# ubus_rev_b.net
KiCad netlist of a schematic drawn in EAGLE
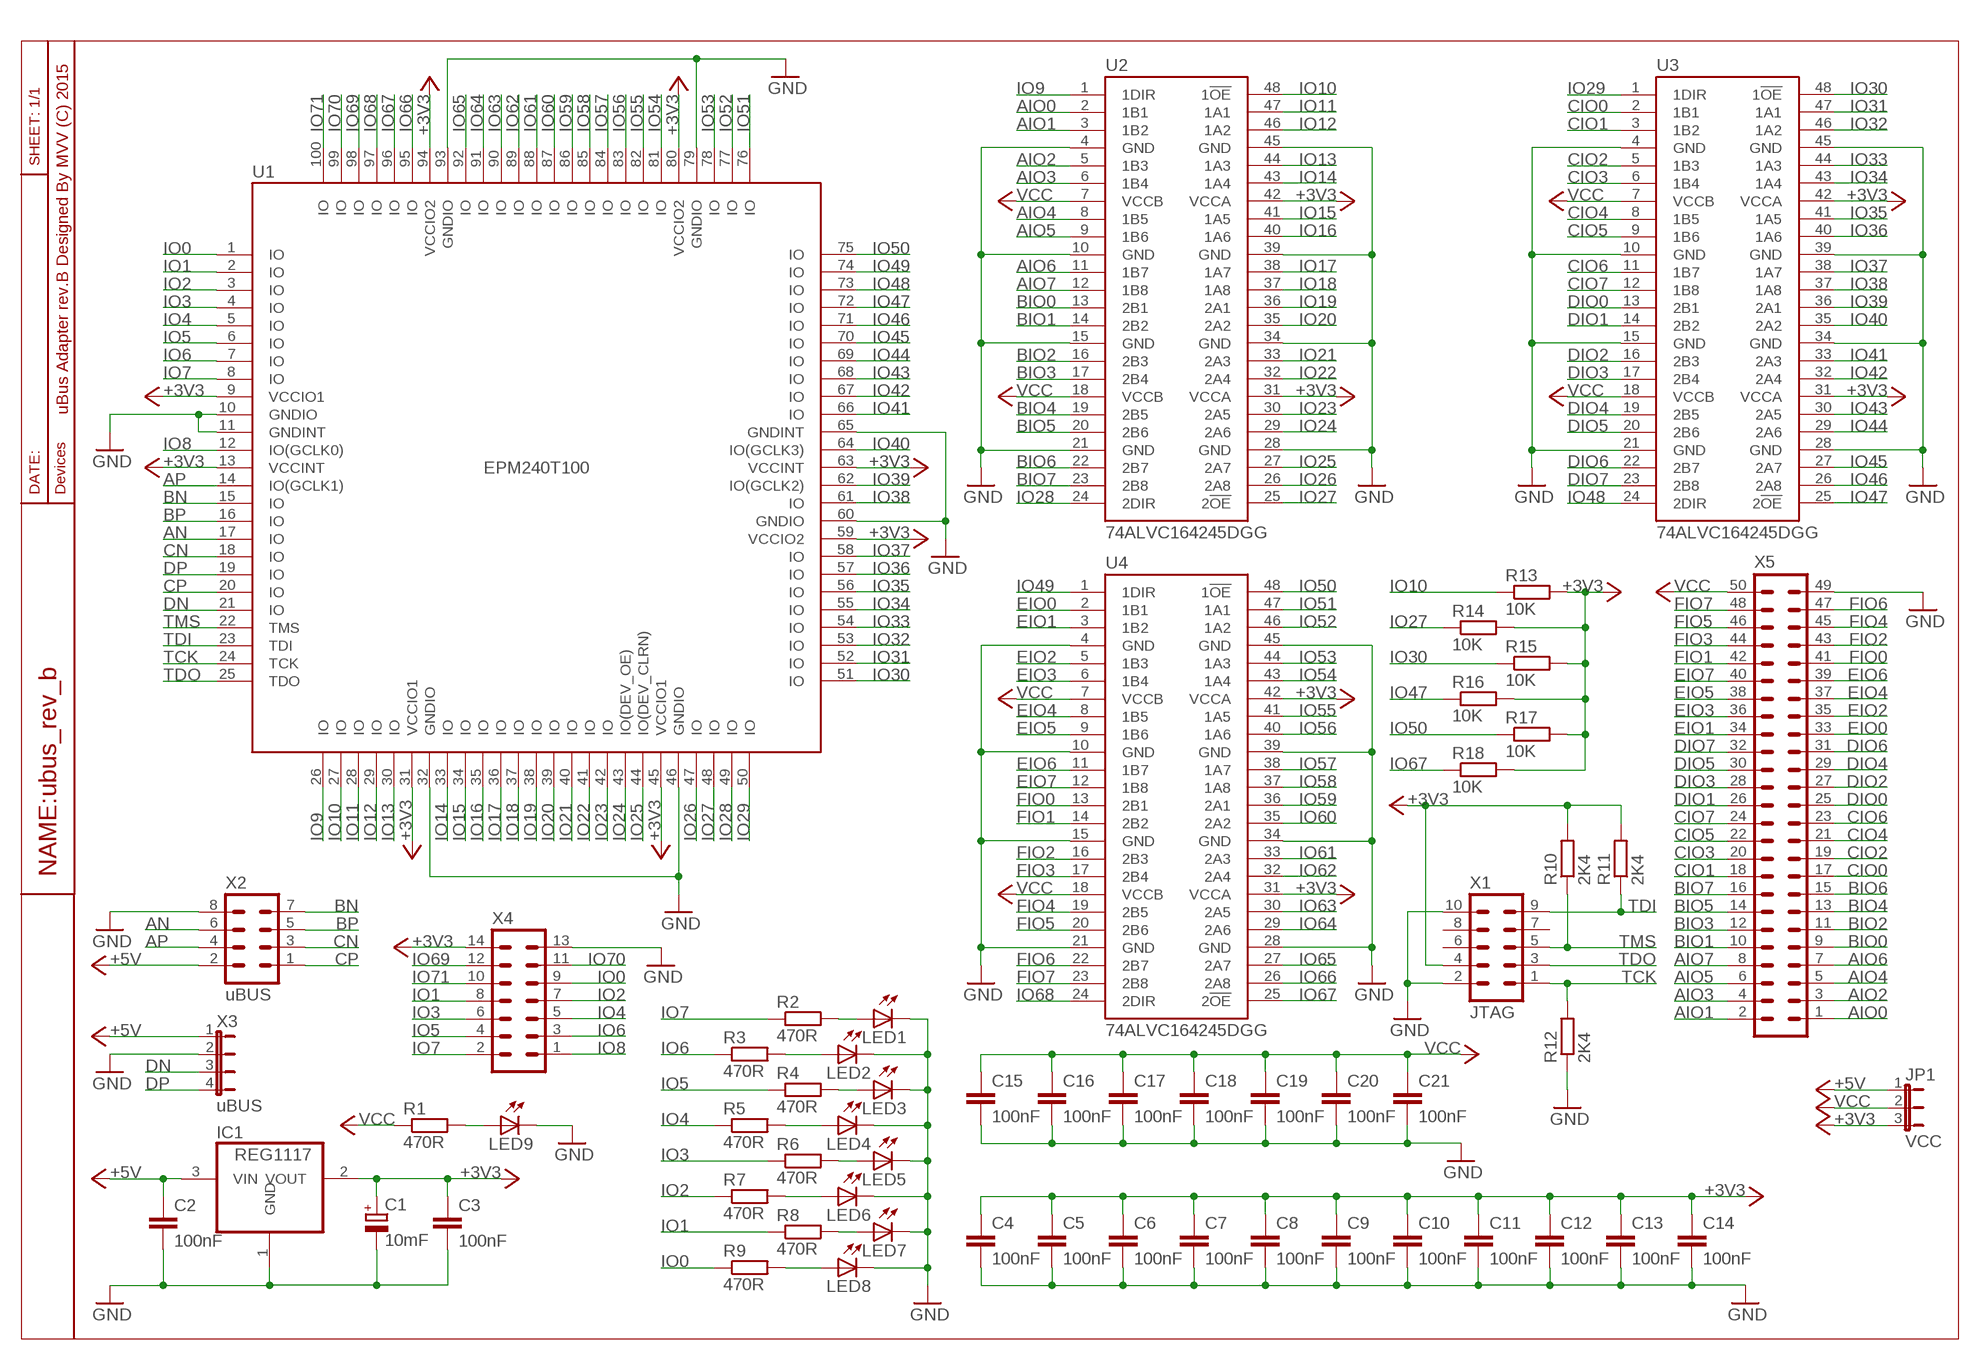
[diagram p0: schematic, sheet 1]

(export (version "E")
  (design (tool "Eeschema 10.0.6"))
  (components
    (comp (ref "C1")
      (value "10mF")
      (footprint "eagle-import:CT6032")
      (libsource (lib "eagle-import") (part "CPOL-EUCT6032"))
    )
    (comp (ref "C2")
      (value "100nF")
      (footprint "eagle-import:C0805")
      (libsource (lib "eagle-import") (part "C-EUC0805"))
    )
    (comp (ref "C3")
      (value "100nF")
      (footprint "eagle-import:C0805")
      (libsource (lib "eagle-import") (part "C-EUC0805"))
    )
    (comp (ref "C4")
      (value "100nF")
      (footprint "eagle-import:C0805")
      (libsource (lib "eagle-import") (part "C-EUC0805"))
    )
    (comp (ref "C5")
      (value "100nF")
      (footprint "eagle-import:C0805")
      (libsource (lib "eagle-import") (part "C-EUC0805"))
    )
    (comp (ref "C6")
      (value "100nF")
      (footprint "eagle-import:C0805")
      (libsource (lib "eagle-import") (part "C-EUC0805"))
    )
    (comp (ref "C7")
      (value "100nF")
      (footprint "eagle-import:C0805")
      (libsource (lib "eagle-import") (part "C-EUC0805"))
    )
    (comp (ref "C8")
      (value "100nF")
      (footprint "eagle-import:C0805")
      (libsource (lib "eagle-import") (part "C-EUC0805"))
    )
    (comp (ref "C9")
      (value "100nF")
      (footprint "eagle-import:C0805")
      (libsource (lib "eagle-import") (part "C-EUC0805"))
    )
    (comp (ref "C10")
      (value "100nF")
      (footprint "eagle-import:C0805")
      (libsource (lib "eagle-import") (part "C-EUC0805"))
    )
    (comp (ref "C11")
      (value "100nF")
      (footprint "eagle-import:C0805")
      (libsource (lib "eagle-import") (part "C-EUC0805"))
    )
    (comp (ref "C12")
      (value "100nF")
      (footprint "eagle-import:C0805")
      (libsource (lib "eagle-import") (part "C-EUC0805"))
    )
    (comp (ref "C13")
      (value "100nF")
      (footprint "eagle-import:C0805")
      (libsource (lib "eagle-import") (part "C-EUC0805"))
    )
    (comp (ref "C14")
      (value "100nF")
      (footprint "eagle-import:C0805")
      (libsource (lib "eagle-import") (part "C-EUC0805"))
    )
    (comp (ref "C15")
      (value "100nF")
      (footprint "eagle-import:C0805")
      (libsource (lib "eagle-import") (part "C-EUC0805"))
    )
    (comp (ref "C16")
      (value "100nF")
      (footprint "eagle-import:C0805")
      (libsource (lib "eagle-import") (part "C-EUC0805"))
    )
    (comp (ref "C17")
      (value "100nF")
      (footprint "eagle-import:C0805")
      (libsource (lib "eagle-import") (part "C-EUC0805"))
    )
    (comp (ref "C18")
      (value "100nF")
      (footprint "eagle-import:C0805")
      (libsource (lib "eagle-import") (part "C-EUC0805"))
    )
    (comp (ref "C19")
      (value "100nF")
      (footprint "eagle-import:C0805")
      (libsource (lib "eagle-import") (part "C-EUC0805"))
    )
    (comp (ref "C20")
      (value "100nF")
      (footprint "eagle-import:C0805")
      (libsource (lib "eagle-import") (part "C-EUC0805"))
    )
    (comp (ref "C21")
      (value "100nF")
      (footprint "eagle-import:C0805")
      (libsource (lib "eagle-import") (part "C-EUC0805"))
    )
    (comp (ref "IC1")
      (value "REG1117")
      (footprint "eagle-import:SOT223")
      (libsource (lib "eagle-import") (part "REG1117"))
    )
    (comp (ref "JP1")
      (value "VCC")
      (footprint "eagle-import:JP2")
      (libsource (lib "eagle-import") (part "JP2E"))
    )
    (comp (ref "LED1")
      (value "LEDCHIPLED_0805")
      (footprint "eagle-import:CHIPLED_0805")
      (libsource (lib "eagle-import") (part "LEDCHIPLED_0805"))
    )
    (comp (ref "LED2")
      (value "LEDCHIPLED_0805")
      (footprint "eagle-import:CHIPLED_0805")
      (libsource (lib "eagle-import") (part "LEDCHIPLED_0805"))
    )
    (comp (ref "LED3")
      (value "LEDCHIPLED_0805")
      (footprint "eagle-import:CHIPLED_0805")
      (libsource (lib "eagle-import") (part "LEDCHIPLED_0805"))
    )
    (comp (ref "LED4")
      (value "LEDCHIPLED_0805")
      (footprint "eagle-import:CHIPLED_0805")
      (libsource (lib "eagle-import") (part "LEDCHIPLED_0805"))
    )
    (comp (ref "LED5")
      (value "LEDCHIPLED_0805")
      (footprint "eagle-import:CHIPLED_0805")
      (libsource (lib "eagle-import") (part "LEDCHIPLED_0805"))
    )
    (comp (ref "LED6")
      (value "LEDCHIPLED_0805")
      (footprint "eagle-import:CHIPLED_0805")
      (libsource (lib "eagle-import") (part "LEDCHIPLED_0805"))
    )
    (comp (ref "LED7")
      (value "LEDCHIPLED_0805")
      (footprint "eagle-import:CHIPLED_0805")
      (libsource (lib "eagle-import") (part "LEDCHIPLED_0805"))
    )
    (comp (ref "LED8")
      (value "LEDCHIPLED_0805")
      (footprint "eagle-import:CHIPLED_0805")
      (libsource (lib "eagle-import") (part "LEDCHIPLED_0805"))
    )
    (comp (ref "LED9")
      (value "LEDCHIPLED_0805")
      (footprint "eagle-import:CHIPLED_0805")
      (libsource (lib "eagle-import") (part "LEDCHIPLED_0805"))
    )
    (comp (ref "R1")
      (value "470R")
      (footprint "eagle-import:R0805")
      (libsource (lib "eagle-import") (part "R-EU_R0805"))
    )
    (comp (ref "R2")
      (value "470R")
      (footprint "eagle-import:R0805")
      (libsource (lib "eagle-import") (part "R-EU_R0805"))
    )
    (comp (ref "R3")
      (value "470R")
      (footprint "eagle-import:R0805")
      (libsource (lib "eagle-import") (part "R-EU_R0805"))
    )
    (comp (ref "R4")
      (value "470R")
      (footprint "eagle-import:R0805")
      (libsource (lib "eagle-import") (part "R-EU_R0805"))
    )
    (comp (ref "R5")
      (value "470R")
      (footprint "eagle-import:R0805")
      (libsource (lib "eagle-import") (part "R-EU_R0805"))
    )
    (comp (ref "R6")
      (value "470R")
      (footprint "eagle-import:R0805")
      (libsource (lib "eagle-import") (part "R-EU_R0805"))
    )
    (comp (ref "R7")
      (value "470R")
      (footprint "eagle-import:R0805")
      (libsource (lib "eagle-import") (part "R-EU_R0805"))
    )
    (comp (ref "R8")
      (value "470R")
      (footprint "eagle-import:R0805")
      (libsource (lib "eagle-import") (part "R-EU_R0805"))
    )
    (comp (ref "R9")
      (value "470R")
      (footprint "eagle-import:R0805")
      (libsource (lib "eagle-import") (part "R-EU_R0805"))
    )
    (comp (ref "R10")
      (value "2K4")
      (footprint "eagle-import:R0805")
      (libsource (lib "eagle-import") (part "R-EU_R0805"))
    )
    (comp (ref "R11")
      (value "2K4")
      (footprint "eagle-import:R0805")
      (libsource (lib "eagle-import") (part "R-EU_R0805"))
    )
    (comp (ref "R12")
      (value "2K4")
      (footprint "eagle-import:R0805")
      (libsource (lib "eagle-import") (part "R-EU_R0805"))
    )
    (comp (ref "R13")
      (value "10K")
      (footprint "eagle-import:R0805")
      (libsource (lib "eagle-import") (part "R-EU_R0805"))
    )
    (comp (ref "R14")
      (value "10K")
      (footprint "eagle-import:R0805")
      (libsource (lib "eagle-import") (part "R-EU_R0805"))
    )
    (comp (ref "R15")
      (value "10K")
      (footprint "eagle-import:R0805")
      (libsource (lib "eagle-import") (part "R-EU_R0805"))
    )
    (comp (ref "R16")
      (value "10K")
      (footprint "eagle-import:R0805")
      (libsource (lib "eagle-import") (part "R-EU_R0805"))
    )
    (comp (ref "R17")
      (value "10K")
      (footprint "eagle-import:R0805")
      (libsource (lib "eagle-import") (part "R-EU_R0805"))
    )
    (comp (ref "R18")
      (value "10K")
      (footprint "eagle-import:R0805")
      (libsource (lib "eagle-import") (part "R-EU_R0805"))
    )
    (comp (ref "U1")
      (value "EPM240T100")
      (footprint "eagle-import:TQFP100")
      (libsource (lib "eagle-import") (part "EPM240T100"))
    )
    (comp (ref "U2")
      (value "74ALVC164245DGG")
      (footprint "eagle-import:TSSOP48DGG")
      (libsource (lib "eagle-import") (part "74ALVC164245DGG"))
    )
    (comp (ref "U3")
      (value "74ALVC164245DGG")
      (footprint "eagle-import:TSSOP48DGG")
      (libsource (lib "eagle-import") (part "74ALVC164245DGG"))
    )
    (comp (ref "U4")
      (value "74ALVC164245DGG")
      (footprint "eagle-import:TSSOP48DGG")
      (libsource (lib "eagle-import") (part "74ALVC164245DGG"))
    )
    (comp (ref "X1")
      (value "JTAG")
      (footprint "eagle-import:ML10")
      (libsource (lib "eagle-import") (part "ML10"))
    )
    (comp (ref "X2")
      (value "uBUS")
      (footprint "eagle-import:MA04-2")
      (libsource (lib "eagle-import") (part "MA04-2"))
    )
    (comp (ref "X3")
      (value "uBUS")
      (footprint "eagle-import:JP4")
      (libsource (lib "eagle-import") (part "JP4E"))
    )
    (comp (ref "X4")
      (value "ML14")
      (footprint "eagle-import:ML14")
      (libsource (lib "eagle-import") (part "ML14"))
    )
    (comp (ref "X5")
      (value "ML50")
      (footprint "eagle-import:ML50")
      (libsource (lib "eagle-import") (part "ML50"))
    )
  )
  (nets
    (net (code "1") (name "+3V3") (class "Default")
      (node (ref "C1") (pin "+") (pinfunction "+_+") (pintype "passive"))
      (node (ref "C10") (pin "1") (pinfunction "1_1") (pintype "passive"))
      (node (ref "C11") (pin "1") (pinfunction "1_1") (pintype "passive"))
      (node (ref "C12") (pin "1") (pinfunction "1_1") (pintype "passive"))
      (node (ref "C13") (pin "1") (pinfunction "1_1") (pintype "passive"))
      (node (ref "C14") (pin "1") (pinfunction "1_1") (pintype "passive"))
      (node (ref "C3") (pin "1") (pinfunction "1_1") (pintype "passive"))
      (node (ref "C4") (pin "1") (pinfunction "1_1") (pintype "passive"))
      (node (ref "C5") (pin "1") (pinfunction "1_1") (pintype "passive"))
      (node (ref "C6") (pin "1") (pinfunction "1_1") (pintype "passive"))
      (node (ref "C7") (pin "1") (pinfunction "1_1") (pintype "passive"))
      (node (ref "C8") (pin "1") (pinfunction "1_1") (pintype "passive"))
      (node (ref "C9") (pin "1") (pinfunction "1_1") (pintype "passive"))
      (node (ref "IC1") (pin "2") (pinfunction "VOUT_2") (pintype "output"))
      (node (ref "JP1") (pin "3") (pinfunction "3_3") (pintype "passive"))
      (node (ref "R10") (pin "2") (pinfunction "2_2") (pintype "passive"))
      (node (ref "R11") (pin "2") (pinfunction "2_2") (pintype "passive"))
      (node (ref "R13") (pin "2") (pinfunction "2_2") (pintype "passive"))
      (node (ref "R14") (pin "2") (pinfunction "2_2") (pintype "passive"))
      (node (ref "R15") (pin "2") (pinfunction "2_2") (pintype "passive"))
      (node (ref "R16") (pin "2") (pinfunction "2_2") (pintype "passive"))
      (node (ref "R17") (pin "2") (pinfunction "2_2") (pintype "passive"))
      (node (ref "R18") (pin "2") (pinfunction "2_2") (pintype "passive"))
      (node (ref "U1") (pin "13") (pinfunction "VCCINT_13") (pintype "power_in"))
      (node (ref "U1") (pin "31") (pinfunction "VCCIO1_31") (pintype "power_in"))
      (node (ref "U1") (pin "45") (pinfunction "VCCIO1_45") (pintype "power_in"))
      (node (ref "U1") (pin "59") (pinfunction "VCCIO2_59") (pintype "power_in"))
      (node (ref "U1") (pin "63") (pinfunction "VCCINT_63") (pintype "power_in"))
      (node (ref "U1") (pin "80") (pinfunction "VCCIO2_80") (pintype "power_in"))
      (node (ref "U1") (pin "9") (pinfunction "VCCIO1_9") (pintype "power_in"))
      (node (ref "U1") (pin "94") (pinfunction "VCCIO2_94") (pintype "power_in"))
      (node (ref "U2") (pin "31") (pinfunction "VCCA_31") (pintype "power_in"))
      (node (ref "U2") (pin "42") (pinfunction "VCCA_42") (pintype "power_in"))
      (node (ref "U3") (pin "31") (pinfunction "VCCA_31") (pintype "power_in"))
      (node (ref "U3") (pin "42") (pinfunction "VCCA_42") (pintype "power_in"))
      (node (ref "U4") (pin "31") (pinfunction "VCCA_31") (pintype "power_in"))
      (node (ref "U4") (pin "42") (pinfunction "VCCA_42") (pintype "power_in"))
      (node (ref "X1") (pin "4") (pinfunction "4_4") (pintype "passive"))
      (node (ref "X4") (pin "14") (pinfunction "14_14") (pintype "passive"))
    )
    (net (code "2") (name "+5V") (class "Default")
      (node (ref "C2") (pin "1") (pinfunction "1_1") (pintype "passive"))
      (node (ref "IC1") (pin "3") (pinfunction "VIN_3") (pintype "input"))
      (node (ref "JP1") (pin "1") (pinfunction "1_1") (pintype "passive"))
      (node (ref "X2") (pin "2") (pinfunction "2_2") (pintype "passive"))
      (node (ref "X3") (pin "1") (pinfunction "1_1") (pintype "passive"))
    )
    (net (code "3") (name "/AIO0") (class "Default")
      (node (ref "U2") (pin "2") (pinfunction "1B1_2") (pintype "bidirectional"))
      (node (ref "X5") (pin "1") (pinfunction "1_1") (pintype "passive"))
    )
    (net (code "4") (name "/AIO1") (class "Default")
      (node (ref "U2") (pin "3") (pinfunction "1B2_3") (pintype "bidirectional"))
      (node (ref "X5") (pin "2") (pinfunction "2_2") (pintype "passive"))
    )
    (net (code "5") (name "/AIO2") (class "Default")
      (node (ref "U2") (pin "5") (pinfunction "1B3_5") (pintype "bidirectional"))
      (node (ref "X5") (pin "3") (pinfunction "3_3") (pintype "passive"))
    )
    (net (code "6") (name "/AIO3") (class "Default")
      (node (ref "U2") (pin "6") (pinfunction "1B4_6") (pintype "bidirectional"))
      (node (ref "X5") (pin "4") (pinfunction "4_4") (pintype "passive"))
    )
    (net (code "7") (name "/AIO4") (class "Default")
      (node (ref "U2") (pin "8") (pinfunction "1B5_8") (pintype "bidirectional"))
      (node (ref "X5") (pin "5") (pinfunction "5_5") (pintype "passive"))
    )
    (net (code "8") (name "/AIO5") (class "Default")
      (node (ref "U2") (pin "9") (pinfunction "1B6_9") (pintype "bidirectional"))
      (node (ref "X5") (pin "6") (pinfunction "6_6") (pintype "passive"))
    )
    (net (code "9") (name "/AIO6") (class "Default")
      (node (ref "U2") (pin "11") (pinfunction "1B7_11") (pintype "bidirectional"))
      (node (ref "X5") (pin "7") (pinfunction "7_7") (pintype "passive"))
    )
    (net (code "10") (name "/AIO7") (class "Default")
      (node (ref "U2") (pin "12") (pinfunction "1B8_12") (pintype "bidirectional"))
      (node (ref "X5") (pin "8") (pinfunction "8_8") (pintype "passive"))
    )
    (net (code "11") (name "/AN") (class "Default")
      (node (ref "U1") (pin "17") (pinfunction "IO_17") (pintype "bidirectional"))
      (node (ref "X2") (pin "6") (pinfunction "6_6") (pintype "passive"))
    )
    (net (code "12") (name "/AP") (class "Default")
      (node (ref "U1") (pin "14") (pinfunction "IO(GCLK1)_14") (pintype "bidirectional"))
      (node (ref "X2") (pin "4") (pinfunction "4_4") (pintype "passive"))
    )
    (net (code "13") (name "/BIO0") (class "Default")
      (node (ref "U2") (pin "13") (pinfunction "2B1_13") (pintype "bidirectional"))
      (node (ref "X5") (pin "9") (pinfunction "9_9") (pintype "passive"))
    )
    (net (code "14") (name "/BIO1") (class "Default")
      (node (ref "U2") (pin "14") (pinfunction "2B2_14") (pintype "bidirectional"))
      (node (ref "X5") (pin "10") (pinfunction "10_10") (pintype "passive"))
    )
    (net (code "15") (name "/BIO2") (class "Default")
      (node (ref "U2") (pin "16") (pinfunction "2B3_16") (pintype "bidirectional"))
      (node (ref "X5") (pin "11") (pinfunction "11_11") (pintype "passive"))
    )
    (net (code "16") (name "/BIO3") (class "Default")
      (node (ref "U2") (pin "17") (pinfunction "2B4_17") (pintype "bidirectional"))
      (node (ref "X5") (pin "12") (pinfunction "12_12") (pintype "passive"))
    )
    (net (code "17") (name "/BIO4") (class "Default")
      (node (ref "U2") (pin "19") (pinfunction "2B5_19") (pintype "bidirectional"))
      (node (ref "X5") (pin "13") (pinfunction "13_13") (pintype "passive"))
    )
    (net (code "18") (name "/BIO5") (class "Default")
      (node (ref "U2") (pin "20") (pinfunction "2B6_20") (pintype "bidirectional"))
      (node (ref "X5") (pin "14") (pinfunction "14_14") (pintype "passive"))
    )
    (net (code "19") (name "/BIO6") (class "Default")
      (node (ref "U2") (pin "22") (pinfunction "2B7_22") (pintype "bidirectional"))
      (node (ref "X5") (pin "15") (pinfunction "15_15") (pintype "passive"))
    )
    (net (code "20") (name "/BIO7") (class "Default")
      (node (ref "U2") (pin "23") (pinfunction "2B8_23") (pintype "bidirectional"))
      (node (ref "X5") (pin "16") (pinfunction "16_16") (pintype "passive"))
    )
    (net (code "21") (name "/BN") (class "Default")
      (node (ref "U1") (pin "15") (pinfunction "IO_15") (pintype "bidirectional"))
      (node (ref "X2") (pin "7") (pinfunction "7_7") (pintype "passive"))
    )
    (net (code "22") (name "/BP") (class "Default")
      (node (ref "U1") (pin "16") (pinfunction "IO_16") (pintype "bidirectional"))
      (node (ref "X2") (pin "5") (pinfunction "5_5") (pintype "passive"))
    )
    (net (code "23") (name "/CIO0") (class "Default")
      (node (ref "U3") (pin "2") (pinfunction "1B1_2") (pintype "bidirectional"))
      (node (ref "X5") (pin "17") (pinfunction "17_17") (pintype "passive"))
    )
    (net (code "24") (name "/CIO1") (class "Default")
      (node (ref "U3") (pin "3") (pinfunction "1B2_3") (pintype "bidirectional"))
      (node (ref "X5") (pin "18") (pinfunction "18_18") (pintype "passive"))
    )
    (net (code "25") (name "/CIO2") (class "Default")
      (node (ref "U3") (pin "5") (pinfunction "1B3_5") (pintype "bidirectional"))
      (node (ref "X5") (pin "19") (pinfunction "19_19") (pintype "passive"))
    )
    (net (code "26") (name "/CIO3") (class "Default")
      (node (ref "U3") (pin "6") (pinfunction "1B4_6") (pintype "bidirectional"))
      (node (ref "X5") (pin "20") (pinfunction "20_20") (pintype "passive"))
    )
    (net (code "27") (name "/CIO4") (class "Default")
      (node (ref "U3") (pin "8") (pinfunction "1B5_8") (pintype "bidirectional"))
      (node (ref "X5") (pin "21") (pinfunction "21_21") (pintype "passive"))
    )
    (net (code "28") (name "/CIO5") (class "Default")
      (node (ref "U3") (pin "9") (pinfunction "1B6_9") (pintype "bidirectional"))
      (node (ref "X5") (pin "22") (pinfunction "22_22") (pintype "passive"))
    )
    (net (code "29") (name "/CIO6") (class "Default")
      (node (ref "U3") (pin "11") (pinfunction "1B7_11") (pintype "bidirectional"))
      (node (ref "X5") (pin "23") (pinfunction "23_23") (pintype "passive"))
    )
    (net (code "30") (name "/CIO7") (class "Default")
      (node (ref "U3") (pin "12") (pinfunction "1B8_12") (pintype "bidirectional"))
      (node (ref "X5") (pin "24") (pinfunction "24_24") (pintype "passive"))
    )
    (net (code "31") (name "/CN") (class "Default")
      (node (ref "U1") (pin "18") (pinfunction "IO_18") (pintype "bidirectional"))
      (node (ref "X2") (pin "3") (pinfunction "3_3") (pintype "passive"))
    )
    (net (code "32") (name "/CP") (class "Default")
      (node (ref "U1") (pin "20") (pinfunction "IO_20") (pintype "bidirectional"))
      (node (ref "X2") (pin "1") (pinfunction "1_1") (pintype "passive"))
    )
    (net (code "33") (name "/DIO0") (class "Default")
      (node (ref "U3") (pin "13") (pinfunction "2B1_13") (pintype "bidirectional"))
      (node (ref "X5") (pin "25") (pinfunction "25_25") (pintype "passive"))
    )
    (net (code "34") (name "/DIO1") (class "Default")
      (node (ref "U3") (pin "14") (pinfunction "2B2_14") (pintype "bidirectional"))
      (node (ref "X5") (pin "26") (pinfunction "26_26") (pintype "passive"))
    )
    (net (code "35") (name "/DIO2") (class "Default")
      (node (ref "U3") (pin "16") (pinfunction "2B3_16") (pintype "bidirectional"))
      (node (ref "X5") (pin "27") (pinfunction "27_27") (pintype "passive"))
    )
    (net (code "36") (name "/DIO3") (class "Default")
      (node (ref "U3") (pin "17") (pinfunction "2B4_17") (pintype "bidirectional"))
      (node (ref "X5") (pin "28") (pinfunction "28_28") (pintype "passive"))
    )
    (net (code "37") (name "/DIO4") (class "Default")
      (node (ref "U3") (pin "19") (pinfunction "2B5_19") (pintype "bidirectional"))
      (node (ref "X5") (pin "29") (pinfunction "29_29") (pintype "passive"))
    )
    (net (code "38") (name "/DIO5") (class "Default")
      (node (ref "U3") (pin "20") (pinfunction "2B6_20") (pintype "bidirectional"))
      (node (ref "X5") (pin "30") (pinfunction "30_30") (pintype "passive"))
    )
    (net (code "39") (name "/DIO6") (class "Default")
      (node (ref "U3") (pin "22") (pinfunction "2B7_22") (pintype "bidirectional"))
      (node (ref "X5") (pin "31") (pinfunction "31_31") (pintype "passive"))
    )
    (net (code "40") (name "/DIO7") (class "Default")
      (node (ref "U3") (pin "23") (pinfunction "2B8_23") (pintype "bidirectional"))
      (node (ref "X5") (pin "32") (pinfunction "32_32") (pintype "passive"))
    )
    (net (code "41") (name "/DN") (class "Default")
      (node (ref "U1") (pin "21") (pinfunction "IO_21") (pintype "bidirectional"))
      (node (ref "X3") (pin "3") (pinfunction "3_3") (pintype "passive"))
    )
    (net (code "42") (name "/DP") (class "Default")
      (node (ref "U1") (pin "19") (pinfunction "IO_19") (pintype "bidirectional"))
      (node (ref "X3") (pin "4") (pinfunction "4_4") (pintype "passive"))
    )
    (net (code "43") (name "/EIO0") (class "Default")
      (node (ref "U4") (pin "2") (pinfunction "1B1_2") (pintype "bidirectional"))
      (node (ref "X5") (pin "33") (pinfunction "33_33") (pintype "passive"))
    )
    (net (code "44") (name "/EIO1") (class "Default")
      (node (ref "U4") (pin "3") (pinfunction "1B2_3") (pintype "bidirectional"))
      (node (ref "X5") (pin "34") (pinfunction "34_34") (pintype "passive"))
    )
    (net (code "45") (name "/EIO2") (class "Default")
      (node (ref "U4") (pin "5") (pinfunction "1B3_5") (pintype "bidirectional"))
      (node (ref "X5") (pin "35") (pinfunction "35_35") (pintype "passive"))
    )
    (net (code "46") (name "/EIO3") (class "Default")
      (node (ref "U4") (pin "6") (pinfunction "1B4_6") (pintype "bidirectional"))
      (node (ref "X5") (pin "36") (pinfunction "36_36") (pintype "passive"))
    )
    (net (code "47") (name "/EIO4") (class "Default")
      (node (ref "U4") (pin "8") (pinfunction "1B5_8") (pintype "bidirectional"))
      (node (ref "X5") (pin "37") (pinfunction "37_37") (pintype "passive"))
    )
    (net (code "48") (name "/EIO5") (class "Default")
      (node (ref "U4") (pin "9") (pinfunction "1B6_9") (pintype "bidirectional"))
      (node (ref "X5") (pin "38") (pinfunction "38_38") (pintype "passive"))
    )
    (net (code "49") (name "/EIO6") (class "Default")
      (node (ref "U4") (pin "11") (pinfunction "1B7_11") (pintype "bidirectional"))
      (node (ref "X5") (pin "39") (pinfunction "39_39") (pintype "passive"))
    )
    (net (code "50") (name "/EIO7") (class "Default")
      (node (ref "U4") (pin "12") (pinfunction "1B8_12") (pintype "bidirectional"))
      (node (ref "X5") (pin "40") (pinfunction "40_40") (pintype "passive"))
    )
    (net (code "51") (name "/FIO0") (class "Default")
      (node (ref "U4") (pin "13") (pinfunction "2B1_13") (pintype "bidirectional"))
      (node (ref "X5") (pin "41") (pinfunction "41_41") (pintype "passive"))
    )
    (net (code "52") (name "/FIO1") (class "Default")
      (node (ref "U4") (pin "14") (pinfunction "2B2_14") (pintype "bidirectional"))
      (node (ref "X5") (pin "42") (pinfunction "42_42") (pintype "passive"))
    )
    (net (code "53") (name "/FIO2") (class "Default")
      (node (ref "U4") (pin "16") (pinfunction "2B3_16") (pintype "bidirectional"))
      (node (ref "X5") (pin "43") (pinfunction "43_43") (pintype "passive"))
    )
    (net (code "54") (name "/FIO3") (class "Default")
      (node (ref "U4") (pin "17") (pinfunction "2B4_17") (pintype "bidirectional"))
      (node (ref "X5") (pin "44") (pinfunction "44_44") (pintype "passive"))
    )
    (net (code "55") (name "/FIO4") (class "Default")
      (node (ref "U4") (pin "19") (pinfunction "2B5_19") (pintype "bidirectional"))
      (node (ref "X5") (pin "45") (pinfunction "45_45") (pintype "passive"))
    )
    (net (code "56") (name "/FIO5") (class "Default")
      (node (ref "U4") (pin "20") (pinfunction "2B6_20") (pintype "bidirectional"))
      (node (ref "X5") (pin "46") (pinfunction "46_46") (pintype "passive"))
    )
    (net (code "57") (name "/FIO6") (class "Default")
      (node (ref "U4") (pin "22") (pinfunction "2B7_22") (pintype "bidirectional"))
      (node (ref "X5") (pin "47") (pinfunction "47_47") (pintype "passive"))
    )
    (net (code "58") (name "/FIO7") (class "Default")
      (node (ref "U4") (pin "23") (pinfunction "2B8_23") (pintype "bidirectional"))
      (node (ref "X5") (pin "48") (pinfunction "48_48") (pintype "passive"))
    )
    (net (code "59") (name "/IO0") (class "Default")
      (node (ref "R9") (pin "1") (pinfunction "1_1") (pintype "passive"))
      (node (ref "U1") (pin "1") (pinfunction "IO_1") (pintype "bidirectional"))
      (node (ref "X4") (pin "9") (pinfunction "9_9") (pintype "passive"))
    )
    (net (code "60") (name "/IO1") (class "Default")
      (node (ref "R8") (pin "1") (pinfunction "1_1") (pintype "passive"))
      (node (ref "U1") (pin "2") (pinfunction "IO_2") (pintype "bidirectional"))
      (node (ref "X4") (pin "8") (pinfunction "8_8") (pintype "passive"))
    )
    (net (code "61") (name "/IO2") (class "Default")
      (node (ref "R7") (pin "1") (pinfunction "1_1") (pintype "passive"))
      (node (ref "U1") (pin "3") (pinfunction "IO_3") (pintype "bidirectional"))
      (node (ref "X4") (pin "7") (pinfunction "7_7") (pintype "passive"))
    )
    (net (code "62") (name "/IO3") (class "Default")
      (node (ref "R6") (pin "1") (pinfunction "1_1") (pintype "passive"))
      (node (ref "U1") (pin "4") (pinfunction "IO_4") (pintype "bidirectional"))
      (node (ref "X4") (pin "6") (pinfunction "6_6") (pintype "passive"))
    )
    (net (code "63") (name "/IO4") (class "Default")
      (node (ref "R5") (pin "1") (pinfunction "1_1") (pintype "passive"))
      (node (ref "U1") (pin "5") (pinfunction "IO_5") (pintype "bidirectional"))
      (node (ref "X4") (pin "5") (pinfunction "5_5") (pintype "passive"))
    )
    (net (code "64") (name "/IO5") (class "Default")
      (node (ref "R4") (pin "1") (pinfunction "1_1") (pintype "passive"))
      (node (ref "U1") (pin "6") (pinfunction "IO_6") (pintype "bidirectional"))
      (node (ref "X4") (pin "4") (pinfunction "4_4") (pintype "passive"))
    )
    (net (code "65") (name "/IO6") (class "Default")
      (node (ref "R3") (pin "1") (pinfunction "1_1") (pintype "passive"))
      (node (ref "U1") (pin "7") (pinfunction "IO_7") (pintype "bidirectional"))
      (node (ref "X4") (pin "3") (pinfunction "3_3") (pintype "passive"))
    )
    (net (code "66") (name "/IO7") (class "Default")
      (node (ref "R2") (pin "1") (pinfunction "1_1") (pintype "passive"))
      (node (ref "U1") (pin "8") (pinfunction "IO_8") (pintype "bidirectional"))
      (node (ref "X4") (pin "2") (pinfunction "2_2") (pintype "passive"))
    )
    (net (code "67") (name "/IO8") (class "Default")
      (node (ref "U1") (pin "12") (pinfunction "IO(GCLK0)_12") (pintype "bidirectional"))
      (node (ref "X4") (pin "1") (pinfunction "1_1") (pintype "passive"))
    )
    (net (code "68") (name "/IO9") (class "Default")
      (node (ref "U1") (pin "26") (pinfunction "IO_26") (pintype "bidirectional"))
      (node (ref "U2") (pin "1") (pinfunction "1DIR_1") (pintype "input"))
    )
    (net (code "69") (name "/IO10") (class "Default")
      (node (ref "R13") (pin "1") (pinfunction "1_1") (pintype "passive"))
      (node (ref "U1") (pin "27") (pinfunction "IO_27") (pintype "bidirectional"))
      (node (ref "U2") (pin "48") (pinfunction "1~{OE}_48") (pintype "input"))
    )
    (net (code "70") (name "/IO11") (class "Default")
      (node (ref "U1") (pin "28") (pinfunction "IO_28") (pintype "bidirectional"))
      (node (ref "U2") (pin "47") (pinfunction "1A1_47") (pintype "bidirectional"))
    )
    (net (code "71") (name "/IO12") (class "Default")
      (node (ref "U1") (pin "29") (pinfunction "IO_29") (pintype "bidirectional"))
      (node (ref "U2") (pin "46") (pinfunction "1A2_46") (pintype "bidirectional"))
    )
    (net (code "72") (name "/IO13") (class "Default")
      (node (ref "U1") (pin "30") (pinfunction "IO_30") (pintype "bidirectional"))
      (node (ref "U2") (pin "44") (pinfunction "1A3_44") (pintype "bidirectional"))
    )
    (net (code "73") (name "/IO14") (class "Default")
      (node (ref "U1") (pin "33") (pinfunction "IO_33") (pintype "bidirectional"))
      (node (ref "U2") (pin "43") (pinfunction "1A4_43") (pintype "bidirectional"))
    )
    (net (code "74") (name "/IO15") (class "Default")
      (node (ref "U1") (pin "34") (pinfunction "IO_34") (pintype "bidirectional"))
      (node (ref "U2") (pin "41") (pinfunction "1A5_41") (pintype "bidirectional"))
    )
    (net (code "75") (name "/IO16") (class "Default")
      (node (ref "U1") (pin "35") (pinfunction "IO_35") (pintype "bidirectional"))
      (node (ref "U2") (pin "40") (pinfunction "1A6_40") (pintype "bidirectional"))
    )
    (net (code "76") (name "/IO17") (class "Default")
      (node (ref "U1") (pin "36") (pinfunction "IO_36") (pintype "bidirectional"))
      (node (ref "U2") (pin "38") (pinfunction "1A7_38") (pintype "bidirectional"))
    )
    (net (code "77") (name "/IO18") (class "Default")
      (node (ref "U1") (pin "37") (pinfunction "IO_37") (pintype "bidirectional"))
      (node (ref "U2") (pin "37") (pinfunction "1A8_37") (pintype "bidirectional"))
    )
    (net (code "78") (name "/IO19") (class "Default")
      (node (ref "U1") (pin "38") (pinfunction "IO_38") (pintype "bidirectional"))
      (node (ref "U2") (pin "36") (pinfunction "2A1_36") (pintype "bidirectional"))
    )
    (net (code "79") (name "/IO20") (class "Default")
      (node (ref "U1") (pin "39") (pinfunction "IO_39") (pintype "bidirectional"))
      (node (ref "U2") (pin "35") (pinfunction "2A2_35") (pintype "bidirectional"))
    )
    (net (code "80") (name "/IO21") (class "Default")
      (node (ref "U1") (pin "40") (pinfunction "IO_40") (pintype "bidirectional"))
      (node (ref "U2") (pin "33") (pinfunction "2A3_33") (pintype "bidirectional"))
    )
    (net (code "81") (name "/IO22") (class "Default")
      (node (ref "U1") (pin "41") (pinfunction "IO_41") (pintype "bidirectional"))
      (node (ref "U2") (pin "32") (pinfunction "2A4_32") (pintype "bidirectional"))
    )
    (net (code "82") (name "/IO23") (class "Default")
      (node (ref "U1") (pin "42") (pinfunction "IO_42") (pintype "bidirectional"))
      (node (ref "U2") (pin "30") (pinfunction "2A5_30") (pintype "bidirectional"))
    )
    (net (code "83") (name "/IO24") (class "Default")
      (node (ref "U1") (pin "43") (pinfunction "IO(DEV_OE)_43") (pintype "bidirectional"))
      (node (ref "U2") (pin "29") (pinfunction "2A6_29") (pintype "bidirectional"))
    )
    (net (code "84") (name "/IO25") (class "Default")
      (node (ref "U1") (pin "44") (pinfunction "IO(DEV_CLRN)_44") (pintype "bidirectional"))
      (node (ref "U2") (pin "27") (pinfunction "2A7_27") (pintype "bidirectional"))
    )
    (net (code "85") (name "/IO26") (class "Default")
      (node (ref "U1") (pin "47") (pinfunction "IO_47") (pintype "bidirectional"))
      (node (ref "U2") (pin "26") (pinfunction "2A8_26") (pintype "bidirectional"))
    )
    (net (code "86") (name "/IO27") (class "Default")
      (node (ref "R14") (pin "1") (pinfunction "1_1") (pintype "passive"))
      (node (ref "U1") (pin "48") (pinfunction "IO_48") (pintype "bidirectional"))
      (node (ref "U2") (pin "25") (pinfunction "2~{OE}_25") (pintype "input"))
    )
    (net (code "87") (name "/IO28") (class "Default")
      (node (ref "U1") (pin "49") (pinfunction "IO_49") (pintype "bidirectional"))
      (node (ref "U2") (pin "24") (pinfunction "2DIR_24") (pintype "bidirectional"))
    )
    (net (code "88") (name "/IO29") (class "Default")
      (node (ref "U1") (pin "50") (pinfunction "IO_50") (pintype "bidirectional"))
      (node (ref "U3") (pin "1") (pinfunction "1DIR_1") (pintype "input"))
    )
    (net (code "89") (name "/IO30") (class "Default")
      (node (ref "R15") (pin "1") (pinfunction "1_1") (pintype "passive"))
      (node (ref "U1") (pin "51") (pinfunction "IO_51") (pintype "bidirectional"))
      (node (ref "U3") (pin "48") (pinfunction "1~{OE}_48") (pintype "input"))
    )
    (net (code "90") (name "/IO31") (class "Default")
      (node (ref "U1") (pin "52") (pinfunction "IO_52") (pintype "bidirectional"))
      (node (ref "U3") (pin "47") (pinfunction "1A1_47") (pintype "bidirectional"))
    )
    (net (code "91") (name "/IO32") (class "Default")
      (node (ref "U1") (pin "53") (pinfunction "IO_53") (pintype "bidirectional"))
      (node (ref "U3") (pin "46") (pinfunction "1A2_46") (pintype "bidirectional"))
    )
    (net (code "92") (name "/IO33") (class "Default")
      (node (ref "U1") (pin "54") (pinfunction "IO_54") (pintype "bidirectional"))
      (node (ref "U3") (pin "44") (pinfunction "1A3_44") (pintype "bidirectional"))
    )
    (net (code "93") (name "/IO34") (class "Default")
      (node (ref "U1") (pin "55") (pinfunction "IO_55") (pintype "bidirectional"))
      (node (ref "U3") (pin "43") (pinfunction "1A4_43") (pintype "bidirectional"))
    )
    (net (code "94") (name "/IO35") (class "Default")
      (node (ref "U1") (pin "56") (pinfunction "IO_56") (pintype "bidirectional"))
      (node (ref "U3") (pin "41") (pinfunction "1A5_41") (pintype "bidirectional"))
    )
    (net (code "95") (name "/IO36") (class "Default")
      (node (ref "U1") (pin "57") (pinfunction "IO_57") (pintype "bidirectional"))
      (node (ref "U3") (pin "40") (pinfunction "1A6_40") (pintype "bidirectional"))
    )
    (net (code "96") (name "/IO37") (class "Default")
      (node (ref "U1") (pin "58") (pinfunction "IO_58") (pintype "bidirectional"))
      (node (ref "U3") (pin "38") (pinfunction "1A7_38") (pintype "bidirectional"))
    )
    (net (code "97") (name "/IO38") (class "Default")
      (node (ref "U1") (pin "61") (pinfunction "IO_61") (pintype "bidirectional"))
      (node (ref "U3") (pin "37") (pinfunction "1A8_37") (pintype "bidirectional"))
    )
    (net (code "98") (name "/IO39") (class "Default")
      (node (ref "U1") (pin "62") (pinfunction "IO(GCLK2)_62") (pintype "bidirectional"))
      (node (ref "U3") (pin "36") (pinfunction "2A1_36") (pintype "bidirectional"))
    )
    (net (code "99") (name "/IO40") (class "Default")
      (node (ref "U1") (pin "64") (pinfunction "IO(GCLK3)_64") (pintype "bidirectional"))
      (node (ref "U3") (pin "35") (pinfunction "2A2_35") (pintype "bidirectional"))
    )
    (net (code "100") (name "/IO41") (class "Default")
      (node (ref "U1") (pin "66") (pinfunction "IO_66") (pintype "bidirectional"))
      (node (ref "U3") (pin "33") (pinfunction "2A3_33") (pintype "bidirectional"))
    )
    (net (code "101") (name "/IO42") (class "Default")
      (node (ref "U1") (pin "67") (pinfunction "IO_67") (pintype "bidirectional"))
      (node (ref "U3") (pin "32") (pinfunction "2A4_32") (pintype "bidirectional"))
    )
    (net (code "102") (name "/IO43") (class "Default")
      (node (ref "U1") (pin "68") (pinfunction "IO_68") (pintype "bidirectional"))
      (node (ref "U3") (pin "30") (pinfunction "2A5_30") (pintype "bidirectional"))
    )
    (net (code "103") (name "/IO44") (class "Default")
      (node (ref "U1") (pin "69") (pinfunction "IO_69") (pintype "bidirectional"))
      (node (ref "U3") (pin "29") (pinfunction "2A6_29") (pintype "bidirectional"))
    )
    (net (code "104") (name "/IO45") (class "Default")
      (node (ref "U1") (pin "70") (pinfunction "IO_70") (pintype "bidirectional"))
      (node (ref "U3") (pin "27") (pinfunction "2A7_27") (pintype "bidirectional"))
    )
    (net (code "105") (name "/IO46") (class "Default")
      (node (ref "U1") (pin "71") (pinfunction "IO_71") (pintype "bidirectional"))
      (node (ref "U3") (pin "26") (pinfunction "2A8_26") (pintype "bidirectional"))
    )
    (net (code "106") (name "/IO47") (class "Default")
      (node (ref "R16") (pin "1") (pinfunction "1_1") (pintype "passive"))
      (node (ref "U1") (pin "72") (pinfunction "IO_72") (pintype "bidirectional"))
      (node (ref "U3") (pin "25") (pinfunction "2~{OE}_25") (pintype "input"))
    )
    (net (code "107") (name "/IO48") (class "Default")
      (node (ref "U1") (pin "73") (pinfunction "IO_73") (pintype "bidirectional"))
      (node (ref "U3") (pin "24") (pinfunction "2DIR_24") (pintype "bidirectional"))
    )
    (net (code "108") (name "/IO49") (class "Default")
      (node (ref "U1") (pin "74") (pinfunction "IO_74") (pintype "bidirectional"))
      (node (ref "U4") (pin "1") (pinfunction "1DIR_1") (pintype "input"))
    )
    (net (code "109") (name "/IO50") (class "Default")
      (node (ref "R17") (pin "1") (pinfunction "1_1") (pintype "passive"))
      (node (ref "U1") (pin "75") (pinfunction "IO_75") (pintype "bidirectional"))
      (node (ref "U4") (pin "48") (pinfunction "1~{OE}_48") (pintype "input"))
    )
    (net (code "110") (name "/IO51") (class "Default")
      (node (ref "U1") (pin "76") (pinfunction "IO_76") (pintype "bidirectional"))
      (node (ref "U4") (pin "47") (pinfunction "1A1_47") (pintype "bidirectional"))
    )
    (net (code "111") (name "/IO52") (class "Default")
      (node (ref "U1") (pin "77") (pinfunction "IO_77") (pintype "bidirectional"))
      (node (ref "U4") (pin "46") (pinfunction "1A2_46") (pintype "bidirectional"))
    )
    (net (code "112") (name "/IO53") (class "Default")
      (node (ref "U1") (pin "78") (pinfunction "IO_78") (pintype "bidirectional"))
      (node (ref "U4") (pin "44") (pinfunction "1A3_44") (pintype "bidirectional"))
    )
    (net (code "113") (name "/IO54") (class "Default")
      (node (ref "U1") (pin "81") (pinfunction "IO_81") (pintype "bidirectional"))
      (node (ref "U4") (pin "43") (pinfunction "1A4_43") (pintype "bidirectional"))
    )
    (net (code "114") (name "/IO55") (class "Default")
      (node (ref "U1") (pin "82") (pinfunction "IO_82") (pintype "bidirectional"))
      (node (ref "U4") (pin "41") (pinfunction "1A5_41") (pintype "bidirectional"))
    )
    (net (code "115") (name "/IO56") (class "Default")
      (node (ref "U1") (pin "83") (pinfunction "IO_83") (pintype "bidirectional"))
      (node (ref "U4") (pin "40") (pinfunction "1A6_40") (pintype "bidirectional"))
    )
    (net (code "116") (name "/IO57") (class "Default")
      (node (ref "U1") (pin "84") (pinfunction "IO_84") (pintype "bidirectional"))
      (node (ref "U4") (pin "38") (pinfunction "1A7_38") (pintype "bidirectional"))
    )
    (net (code "117") (name "/IO58") (class "Default")
      (node (ref "U1") (pin "85") (pinfunction "IO_85") (pintype "bidirectional"))
      (node (ref "U4") (pin "37") (pinfunction "1A8_37") (pintype "bidirectional"))
    )
    (net (code "118") (name "/IO59") (class "Default")
      (node (ref "U1") (pin "86") (pinfunction "IO_86") (pintype "bidirectional"))
      (node (ref "U4") (pin "36") (pinfunction "2A1_36") (pintype "bidirectional"))
    )
    (net (code "119") (name "/IO60") (class "Default")
      (node (ref "U1") (pin "87") (pinfunction "IO_87") (pintype "bidirectional"))
      (node (ref "U4") (pin "35") (pinfunction "2A2_35") (pintype "bidirectional"))
    )
    (net (code "120") (name "/IO61") (class "Default")
      (node (ref "U1") (pin "88") (pinfunction "IO_88") (pintype "bidirectional"))
      (node (ref "U4") (pin "33") (pinfunction "2A3_33") (pintype "bidirectional"))
    )
    (net (code "121") (name "/IO62") (class "Default")
      (node (ref "U1") (pin "89") (pinfunction "IO_89") (pintype "bidirectional"))
      (node (ref "U4") (pin "32") (pinfunction "2A4_32") (pintype "bidirectional"))
    )
    (net (code "122") (name "/IO63") (class "Default")
      (node (ref "U1") (pin "90") (pinfunction "IO_90") (pintype "bidirectional"))
      (node (ref "U4") (pin "30") (pinfunction "2A5_30") (pintype "bidirectional"))
    )
    (net (code "123") (name "/IO64") (class "Default")
      (node (ref "U1") (pin "91") (pinfunction "IO_91") (pintype "bidirectional"))
      (node (ref "U4") (pin "29") (pinfunction "2A6_29") (pintype "bidirectional"))
    )
    (net (code "124") (name "/IO65") (class "Default")
      (node (ref "U1") (pin "92") (pinfunction "IO_92") (pintype "bidirectional"))
      (node (ref "U4") (pin "27") (pinfunction "2A7_27") (pintype "bidirectional"))
    )
    (net (code "125") (name "/IO66") (class "Default")
      (node (ref "U1") (pin "95") (pinfunction "IO_95") (pintype "bidirectional"))
      (node (ref "U4") (pin "26") (pinfunction "2A8_26") (pintype "bidirectional"))
    )
    (net (code "126") (name "/IO67") (class "Default")
      (node (ref "R18") (pin "1") (pinfunction "1_1") (pintype "passive"))
      (node (ref "U1") (pin "96") (pinfunction "IO_96") (pintype "bidirectional"))
      (node (ref "U4") (pin "25") (pinfunction "2~{OE}_25") (pintype "input"))
    )
    (net (code "127") (name "/IO68") (class "Default")
      (node (ref "U1") (pin "97") (pinfunction "IO_97") (pintype "bidirectional"))
      (node (ref "U4") (pin "24") (pinfunction "2DIR_24") (pintype "bidirectional"))
    )
    (net (code "128") (name "/IO69") (class "Default")
      (node (ref "U1") (pin "98") (pinfunction "IO_98") (pintype "bidirectional"))
      (node (ref "X4") (pin "12") (pinfunction "12_12") (pintype "passive"))
    )
    (net (code "129") (name "/IO70") (class "Default")
      (node (ref "U1") (pin "99") (pinfunction "IO_99") (pintype "bidirectional"))
      (node (ref "X4") (pin "11") (pinfunction "11_11") (pintype "passive"))
    )
    (net (code "130") (name "/IO71") (class "Default")
      (node (ref "U1") (pin "100") (pinfunction "IO_100") (pintype "bidirectional"))
      (node (ref "X4") (pin "10") (pinfunction "10_10") (pintype "passive"))
    )
    (net (code "131") (name "/TCK") (class "Default")
      (node (ref "R12") (pin "2") (pinfunction "2_2") (pintype "passive"))
      (node (ref "U1") (pin "24") (pinfunction "TCK_24") (pintype "bidirectional"))
      (node (ref "X1") (pin "1") (pinfunction "1_1") (pintype "passive"))
    )
    (net (code "132") (name "/TDI") (class "Default")
      (node (ref "R11") (pin "1") (pinfunction "1_1") (pintype "passive"))
      (node (ref "U1") (pin "23") (pinfunction "TDI_23") (pintype "bidirectional"))
      (node (ref "X1") (pin "9") (pinfunction "9_9") (pintype "passive"))
    )
    (net (code "133") (name "/TDO") (class "Default")
      (node (ref "U1") (pin "25") (pinfunction "TDO_25") (pintype "bidirectional"))
      (node (ref "X1") (pin "3") (pinfunction "3_3") (pintype "passive"))
    )
    (net (code "134") (name "/TMS") (class "Default")
      (node (ref "R10") (pin "1") (pinfunction "1_1") (pintype "passive"))
      (node (ref "U1") (pin "22") (pinfunction "TMS_22") (pintype "bidirectional"))
      (node (ref "X1") (pin "5") (pinfunction "5_5") (pintype "passive"))
    )
    (net (code "135") (name "GND") (class "Default")
      (node (ref "C1") (pin "-") (pinfunction "-_-") (pintype "passive"))
      (node (ref "C10") (pin "2") (pinfunction "2_2") (pintype "passive"))
      (node (ref "C11") (pin "2") (pinfunction "2_2") (pintype "passive"))
      (node (ref "C12") (pin "2") (pinfunction "2_2") (pintype "passive"))
      (node (ref "C13") (pin "2") (pinfunction "2_2") (pintype "passive"))
      (node (ref "C14") (pin "2") (pinfunction "2_2") (pintype "passive"))
      (node (ref "C15") (pin "2") (pinfunction "2_2") (pintype "passive"))
      (node (ref "C16") (pin "2") (pinfunction "2_2") (pintype "passive"))
      (node (ref "C17") (pin "2") (pinfunction "2_2") (pintype "passive"))
      (node (ref "C18") (pin "2") (pinfunction "2_2") (pintype "passive"))
      (node (ref "C19") (pin "2") (pinfunction "2_2") (pintype "passive"))
      (node (ref "C2") (pin "2") (pinfunction "2_2") (pintype "passive"))
      (node (ref "C20") (pin "2") (pinfunction "2_2") (pintype "passive"))
      (node (ref "C21") (pin "2") (pinfunction "2_2") (pintype "passive"))
      (node (ref "C3") (pin "2") (pinfunction "2_2") (pintype "passive"))
      (node (ref "C4") (pin "2") (pinfunction "2_2") (pintype "passive"))
      (node (ref "C5") (pin "2") (pinfunction "2_2") (pintype "passive"))
      (node (ref "C6") (pin "2") (pinfunction "2_2") (pintype "passive"))
      (node (ref "C7") (pin "2") (pinfunction "2_2") (pintype "passive"))
      (node (ref "C8") (pin "2") (pinfunction "2_2") (pintype "passive"))
      (node (ref "C9") (pin "2") (pinfunction "2_2") (pintype "passive"))
      (node (ref "IC1") (pin "1") (pinfunction "GND_1") (pintype "power_in"))
      (node (ref "LED1") (pin "C") (pinfunction "C_C") (pintype "passive"))
      (node (ref "LED2") (pin "C") (pinfunction "C_C") (pintype "passive"))
      (node (ref "LED3") (pin "C") (pinfunction "C_C") (pintype "passive"))
      (node (ref "LED4") (pin "C") (pinfunction "C_C") (pintype "passive"))
      (node (ref "LED5") (pin "C") (pinfunction "C_C") (pintype "passive"))
      (node (ref "LED6") (pin "C") (pinfunction "C_C") (pintype "passive"))
      (node (ref "LED7") (pin "C") (pinfunction "C_C") (pintype "passive"))
      (node (ref "LED8") (pin "C") (pinfunction "C_C") (pintype "passive"))
      (node (ref "LED9") (pin "C") (pinfunction "C_C") (pintype "passive"))
      (node (ref "R12") (pin "1") (pinfunction "1_1") (pintype "passive"))
      (node (ref "U1") (pin "10") (pinfunction "GNDIO_10") (pintype "power_in"))
      (node (ref "U1") (pin "11") (pinfunction "GNDINT_11") (pintype "power_in"))
      (node (ref "U1") (pin "32") (pinfunction "GNDIO_32") (pintype "power_in"))
      (node (ref "U1") (pin "46") (pinfunction "GNDIO_46") (pintype "power_in"))
      (node (ref "U1") (pin "60") (pinfunction "GNDIO_60") (pintype "power_in"))
      (node (ref "U1") (pin "65") (pinfunction "GNDINT_65") (pintype "power_in"))
      (node (ref "U1") (pin "79") (pinfunction "GNDIO_79") (pintype "power_in"))
      (node (ref "U1") (pin "93") (pinfunction "GNDIO_93") (pintype "power_in"))
      (node (ref "U2") (pin "10") (pinfunction "GND_10") (pintype "bidirectional"))
      (node (ref "U2") (pin "15") (pinfunction "GND_15") (pintype "bidirectional"))
      (node (ref "U2") (pin "21") (pinfunction "GND_21") (pintype "power_in"))
      (node (ref "U2") (pin "28") (pinfunction "GND_28") (pintype "power_in"))
      (node (ref "U2") (pin "34") (pinfunction "GND_34") (pintype "power_in"))
      (node (ref "U2") (pin "39") (pinfunction "GND_39") (pintype "power_in"))
      (node (ref "U2") (pin "4") (pinfunction "GND_4") (pintype "power_in"))
      (node (ref "U2") (pin "45") (pinfunction "GND_45") (pintype "power_in"))
      (node (ref "U3") (pin "10") (pinfunction "GND_10") (pintype "bidirectional"))
      (node (ref "U3") (pin "15") (pinfunction "GND_15") (pintype "bidirectional"))
      (node (ref "U3") (pin "21") (pinfunction "GND_21") (pintype "power_in"))
      (node (ref "U3") (pin "28") (pinfunction "GND_28") (pintype "power_in"))
      (node (ref "U3") (pin "34") (pinfunction "GND_34") (pintype "power_in"))
      (node (ref "U3") (pin "39") (pinfunction "GND_39") (pintype "power_in"))
      (node (ref "U3") (pin "4") (pinfunction "GND_4") (pintype "power_in"))
      (node (ref "U3") (pin "45") (pinfunction "GND_45") (pintype "power_in"))
      (node (ref "U4") (pin "10") (pinfunction "GND_10") (pintype "bidirectional"))
      (node (ref "U4") (pin "15") (pinfunction "GND_15") (pintype "bidirectional"))
      (node (ref "U4") (pin "21") (pinfunction "GND_21") (pintype "power_in"))
      (node (ref "U4") (pin "28") (pinfunction "GND_28") (pintype "power_in"))
      (node (ref "U4") (pin "34") (pinfunction "GND_34") (pintype "power_in"))
      (node (ref "U4") (pin "39") (pinfunction "GND_39") (pintype "power_in"))
      (node (ref "U4") (pin "4") (pinfunction "GND_4") (pintype "power_in"))
      (node (ref "U4") (pin "45") (pinfunction "GND_45") (pintype "power_in"))
      (node (ref "X1") (pin "10") (pinfunction "10_10") (pintype "passive"))
      (node (ref "X1") (pin "2") (pinfunction "2_2") (pintype "passive"))
      (node (ref "X2") (pin "8") (pinfunction "8_8") (pintype "passive"))
      (node (ref "X3") (pin "2") (pinfunction "2_2") (pintype "passive"))
      (node (ref "X4") (pin "13") (pinfunction "13_13") (pintype "passive"))
      (node (ref "X5") (pin "49") (pinfunction "49_49") (pintype "passive"))
    )
    (net (code "136") (name "Net-(LED1-PadA)") (class "Default")
      (node (ref "LED1") (pin "A") (pinfunction "A_A") (pintype "passive"))
      (node (ref "R2") (pin "2") (pinfunction "2_2") (pintype "passive"))
    )
    (net (code "137") (name "Net-(LED2-PadA)") (class "Default")
      (node (ref "LED2") (pin "A") (pinfunction "A_A") (pintype "passive"))
      (node (ref "R3") (pin "2") (pinfunction "2_2") (pintype "passive"))
    )
    (net (code "138") (name "Net-(LED3-PadA)") (class "Default")
      (node (ref "LED3") (pin "A") (pinfunction "A_A") (pintype "passive"))
      (node (ref "R4") (pin "2") (pinfunction "2_2") (pintype "passive"))
    )
    (net (code "139") (name "Net-(LED4-PadA)") (class "Default")
      (node (ref "LED4") (pin "A") (pinfunction "A_A") (pintype "passive"))
      (node (ref "R5") (pin "2") (pinfunction "2_2") (pintype "passive"))
    )
    (net (code "140") (name "Net-(LED5-PadA)") (class "Default")
      (node (ref "LED5") (pin "A") (pinfunction "A_A") (pintype "passive"))
      (node (ref "R6") (pin "2") (pinfunction "2_2") (pintype "passive"))
    )
    (net (code "141") (name "Net-(LED6-PadA)") (class "Default")
      (node (ref "LED6") (pin "A") (pinfunction "A_A") (pintype "passive"))
      (node (ref "R7") (pin "2") (pinfunction "2_2") (pintype "passive"))
    )
    (net (code "142") (name "Net-(LED7-PadA)") (class "Default")
      (node (ref "LED7") (pin "A") (pinfunction "A_A") (pintype "passive"))
      (node (ref "R8") (pin "2") (pinfunction "2_2") (pintype "passive"))
    )
    (net (code "143") (name "Net-(LED8-PadA)") (class "Default")
      (node (ref "LED8") (pin "A") (pinfunction "A_A") (pintype "passive"))
      (node (ref "R9") (pin "2") (pinfunction "2_2") (pintype "passive"))
    )
    (net (code "144") (name "Net-(LED9-PadA)") (class "Default")
      (node (ref "LED9") (pin "A") (pinfunction "A_A") (pintype "passive"))
      (node (ref "R1") (pin "2") (pinfunction "2_2") (pintype "passive"))
    )
    (net (code "145") (name "VCC") (class "Default")
      (node (ref "C15") (pin "1") (pinfunction "1_1") (pintype "passive"))
      (node (ref "C16") (pin "1") (pinfunction "1_1") (pintype "passive"))
      (node (ref "C17") (pin "1") (pinfunction "1_1") (pintype "passive"))
      (node (ref "C18") (pin "1") (pinfunction "1_1") (pintype "passive"))
      (node (ref "C19") (pin "1") (pinfunction "1_1") (pintype "passive"))
      (node (ref "C20") (pin "1") (pinfunction "1_1") (pintype "passive"))
      (node (ref "C21") (pin "1") (pinfunction "1_1") (pintype "passive"))
      (node (ref "JP1") (pin "2") (pinfunction "2_2") (pintype "passive"))
      (node (ref "R1") (pin "1") (pinfunction "1_1") (pintype "passive"))
      (node (ref "U2") (pin "18") (pinfunction "VCCB_18") (pintype "power_in"))
      (node (ref "U2") (pin "7") (pinfunction "VCCB_7") (pintype "power_in"))
      (node (ref "U3") (pin "18") (pinfunction "VCCB_18") (pintype "power_in"))
      (node (ref "U3") (pin "7") (pinfunction "VCCB_7") (pintype "power_in"))
      (node (ref "U4") (pin "18") (pinfunction "VCCB_18") (pintype "power_in"))
      (node (ref "U4") (pin "7") (pinfunction "VCCB_7") (pintype "power_in"))
      (node (ref "X5") (pin "50") (pinfunction "50_50") (pintype "passive"))
    )
    (net (code "146") (name "unconnected-(X1-Pad6)") (class "Default")
      (node (ref "X1") (pin "6") (pinfunction "6_6") (pintype "passive"))
    )
    (net (code "147") (name "unconnected-(X1-Pad7)") (class "Default")
      (node (ref "X1") (pin "7") (pinfunction "7_7") (pintype "passive"))
    )
    (net (code "148") (name "unconnected-(X1-Pad8)") (class "Default")
      (node (ref "X1") (pin "8") (pinfunction "8_8") (pintype "passive"))
    )
  )
)
